# ARDUINO_UNO_CH340.net
KiCad netlist of a schematic drawn in Altium Designer
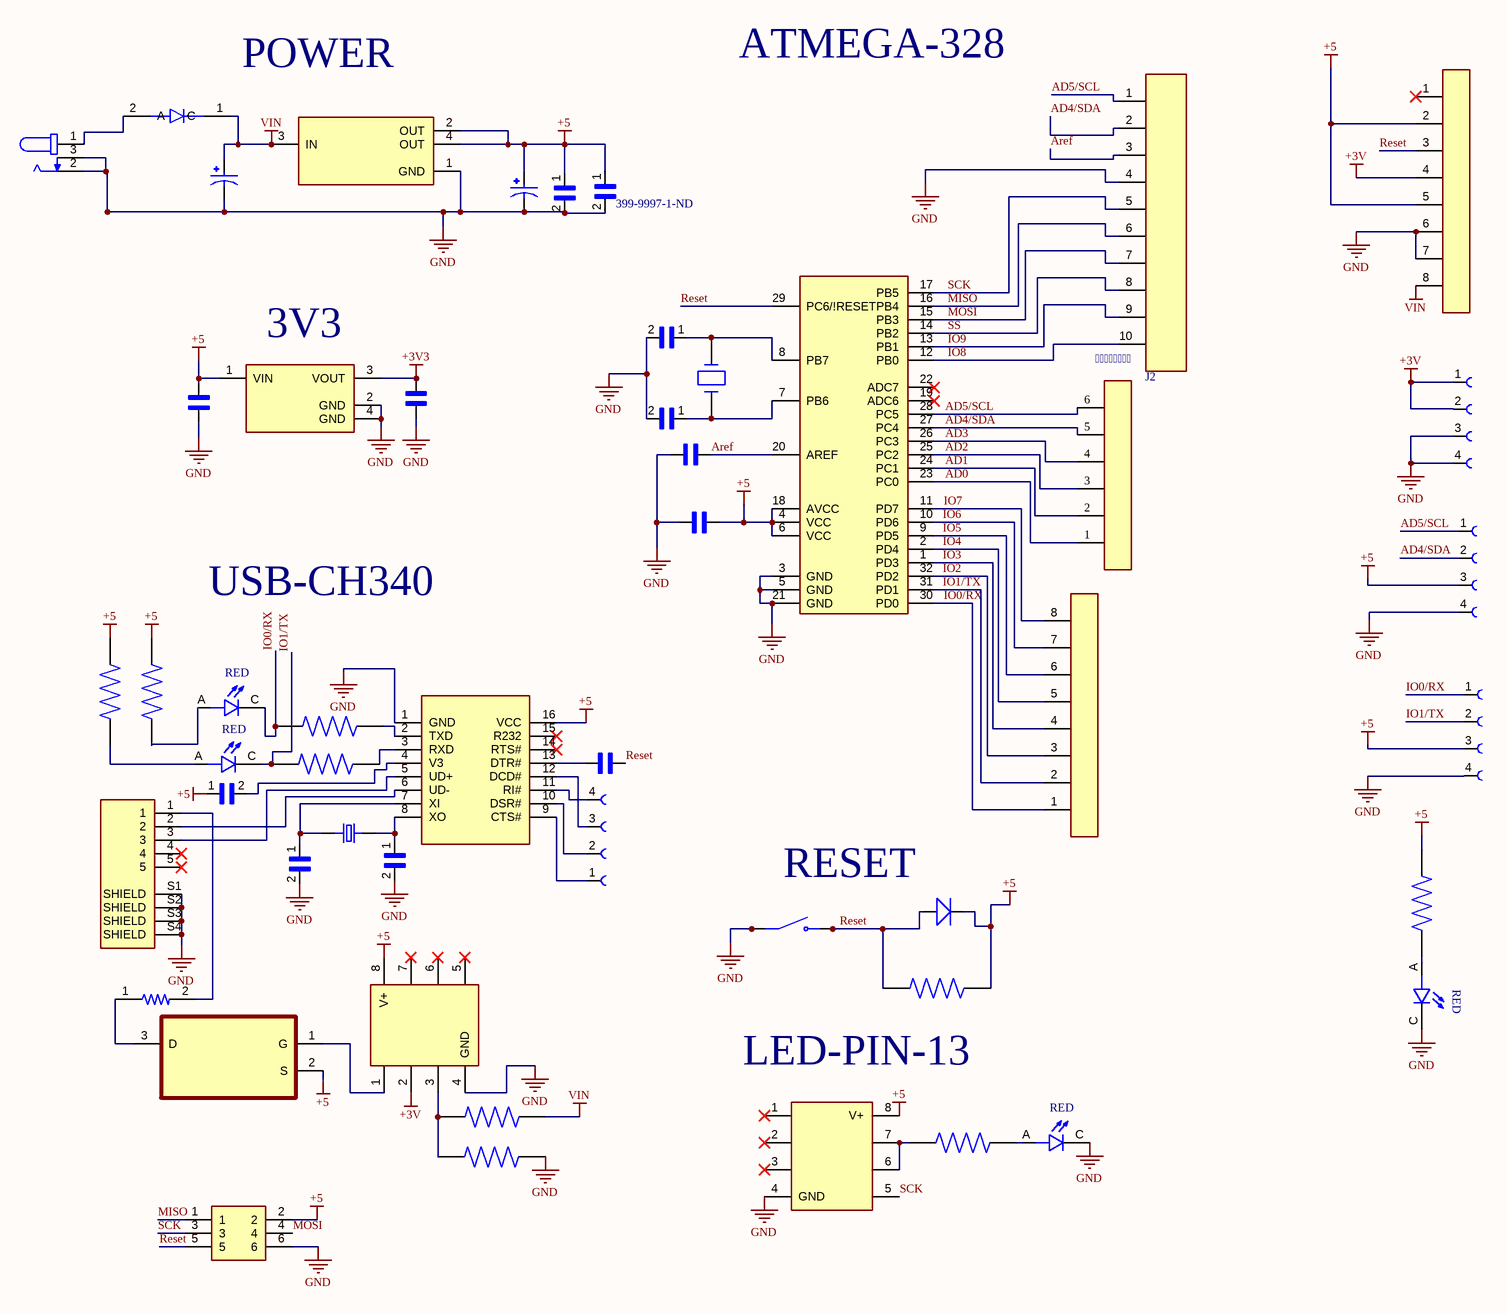
[diagram p0: ARDUINO_UNO_CH340.SchDoc]

(export (version "E")
  (design (tool "Eeschema 10.0.6"))
  (components
    (comp (ref "C1")
      (value "CAP ALUM 47UF 20% 25V SMD")
      (footprint "CAP_25SVPD47M")
      (description "47 µF 25 V Aluminum Electrolytic Capacitors Radial, Can - SMD - 3000 Hrs @ 105°C")
      (fields (field (name "MP") "25SVPD47M"))
      (libsource (lib "ARDUINO_UNO_CH340") (part "25SVPD47M"))
    )
    (comp (ref "C2")
      (value "CAP ALUM 47UF 20% 25V SMD")
      (footprint "CAP_25SVPD47M")
      (description "47 µF 25 V Aluminum Electrolytic Capacitors Radial, Can - SMD - 3000 Hrs @ 105°C")
      (fields (field (name "MP") "25SVPD47M"))
      (libsource (lib "ARDUINO_UNO_CH340") (part "25SVPD47M"))
    )
    (comp (ref "C3")
      (value "C0805J104K5RACTU")
      (footprint "CAPC2012X88N")
      (description "CAP MLCC, 0.1UF, 50V, X7R, 10%, 0805; Product Range: KEMET - J Series; Capacitance")
      (fields (field (name "MF") "KEMET"))
      (libsource (lib "ARDUINO_UNO_CH340") (part "C0805J104K5RACTU"))
    )
    (comp (ref "C4")
      (value "C0805J104K5RACTU")
      (footprint "CAPC2012X88N")
      (description "CAP MLCC, 0.1UF, 50V, X7R, 10%, 0805; Product Range: KEMET - J Series; Capacitance")
      (fields (field (name "MF") "KEMET") (field (name "SUPPLIER PART NUMBER 1") "399-9997-1-ND"))
      (libsource (lib "ARDUINO_UNO_CH340") (part "C0805J104K5RACTU"))
    )
    (comp (ref "C5")
      (value "CAP CER 25PF 100V NP0 0805")
      (footprint "CAPC2012X94N")
      (description "25 pF ±2% 100V Ceramic Capacitor C0G, NP0 0805 (2012 Metric)")
      (fields (field (name "MP") "08051A250GAT2A"))
      (libsource (lib "ARDUINO_UNO_CH340") (part "08051A250GAT2A"))
    )
    (comp (ref "C6")
      (value "CAP CER 25PF 100V NP0 0805")
      (footprint "CAPC2012X94N")
      (description "25 pF ±2% 100V Ceramic Capacitor C0G, NP0 0805 (2012 Metric)")
      (fields (field (name "MP") "08051A250GAT2A"))
      (libsource (lib "ARDUINO_UNO_CH340") (part "08051A250GAT2A"))
    )
    (comp (ref "C7")
      (value "885012209041")
      (footprint "WCAP-CSGP_885012209041")
      (libsource (lib "") (part "885012209041_1"))
    )
    (comp (ref "C8")
      (value "885012209041")
      (footprint "WCAP-CSGP_885012209041")
      (libsource (lib "") (part "885012209041_1"))
    )
    (comp (ref "C9")
      (value "885012209041")
      (footprint "WCAP-CSGP_885012209041")
      (libsource (lib "") (part "885012209041_2"))
    )
    (comp (ref "C10")
      (value "885012209041")
      (footprint "WCAP-CSGP_885012209041")
      (libsource (lib "ARDUINO_UNO_CH340") (part "885012209041"))
    )
    (comp (ref "C11")
      (value "CAP CER 0805 10NF 50V C0G 1%")
      (footprint "CAPC2012X88N")
      (description "±1% 50V Ceramic Capacitor C0G, NP0 0805 (2012 Metric)")
      (fields (field (name "MF") "KEMET") (field (name "MP") "C0805J104K5RACTU"))
      (libsource (lib "ARDUINO_UNO_CH340") (part "C0805C103F5GEC-ND"))
    )
    (comp (ref "C12")
      (value "885012209041")
      (footprint "WCAP-CSGP_885012209041")
      (libsource (lib "ARDUINO_UNO_CH340") (part "885012209041"))
    )
    (comp (ref "C13")
      (value "CAP CER 25PF 100V NP0 0805")
      (footprint "CAPC2012X94N")
      (description "25 pF ±2% 100V Ceramic Capacitor C0G, NP0 0805 (2012 Metric)")
      (fields (field (name "MP") "08051A250GAT2A"))
      (libsource (lib "") (part "08051A250GAT2A_1"))
    )
    (comp (ref "C14")
      (value "CAP CER 25PF 100V NP0 0805")
      (footprint "CAPC2012X94N")
      (description "25 pF ±2% 100V Ceramic Capacitor C0G, NP0 0805 (2012 Metric)")
      (fields (field (name "MP") "08051A250GAT2A"))
      (libsource (lib "") (part "08051A250GAT2A_1"))
    )
    (comp (ref "CO1")
      (value "CRYSTAL 16.0000MHZ 18PF SMD")
      (footprint "XTAL_ABLS2-24.000MHZ-D4YF-T")
      (description "24MHz Â±30ppm Crystal 18pF 40 Ohms HC-49/US")
      (fields (field (name "MP") "ABLS2-24.000MHZ-D4YF-T") (field (name "MF") "Abracon"))
      (libsource (lib "ARDUINO_UNO_CH340") (part "ABLS2-24.000MHZ-D4YF-T"))
    )
    (comp (ref "CP1")
      (value "CONN PWR JACK 2X5.5MM SOLDER")
      (footprint "POWERJACK_CUI_PJ-002A")
      (description "Power Barrel Connector Jack 2.10mm ID (0.083\"), 5.50mm OD (0.217\") Through Hole, Right Angle")
      (libsource (lib "ARDUINO_UNO_CH340") (part "CP-002A-ND"))
    )
    (comp (ref "D1")
      (value "S1M-FDITR-ND")
      (footprint "DIODE_DIOM4226X244N")
      (description "DIODE GEN PURP 1KV 1A SMA")
      (fields (field (name "MF") "ON Semiconductor") (field (name "MP") "ES1G"))
      (libsource (lib "ARDUINO_UNO_CH340") (part "DIODE_S1G"))
    )
    (comp (ref "D2")
      (value "7012X1")
      (footprint "LED_7012X1")
      (description "Red LED Indication - Discrete 1.7V 0805 (2012 Metric)")
      (libsource (lib "ARDUINO_UNO_CH340") (part "7012X1"))
    )
    (comp (ref "D3")
      (value "7012X1")
      (footprint "LED_7012X1")
      (description "Red LED Indication - Discrete 1.7V 0805 (2012 Metric)")
      (libsource (lib "ARDUINO_UNO_CH340") (part "7012X1"))
    )
    (comp (ref "D4")
      (value "DIODE GEN PURP 100V 150MA 1206")
      (footprint "DIODE")
      (description "Diode Standard 100V 150mA Surface Mount 1206")
      (fields (field (name "MP") "CD1206-S01575") (field (name "MF") "Bourns"))
      (libsource (lib "ARDUINO_UNO_CH340") (part "CD1206-S01575"))
    )
    (comp (ref "D5")
      (value "7012X1")
      (footprint "LED_7012X1")
      (description "Red LED Indication - Discrete 1.7V 0805 (2012 Metric)")
      (libsource (lib "ARDUINO_UNO_CH340") (part "7012X1"))
    )
    (comp (ref "D6")
      (value "7012X1")
      (footprint "LED_7012X1")
      (description "Red LED Indication - Discrete 1.7V 0805 (2012 Metric)")
      (libsource (lib "ARDUINO_UNO_CH340") (part "7012X1"))
    )
    (comp (ref "J1")
      (value "Conn_Sullins_PPTC081LFBN-RC_eec")
      (footprint "Sullins_PPTC081LFBN-RC_0")
      (description "CONN HEADER FEMALE 8POS .1\" TIN")
      (fields (field (name "MANUFACTURER") "Sullins") (field (name "DIGIKEY PART NUMBER") "S7006-ND"))
      (libsource (lib "ARDUINO_UNO_CH340") (part "Conn_Sullins_PPTC081LFBN-RC_eec"))
    )
    (comp (ref "J2")
      (value "Conn_Sullins_PPTC101LFBN-RC_eec")
      (footprint "Sullins_PPTC101LFBN-RC_0 - duplicate2")
      (description "CONN HEADER FEMALE 10POS.1\" TIN")
      (fields
        (field (name "MANUFACTURER") "Sullins")
        (field (name "OCTOPART PART NUMBER") "a3ed6ae3a4397c2a")
      )
      (libsource (lib "ARDUINO_UNO_CH340") (part "Conn_Sullins_PPTC101LFBN-RC_eec"))
    )
    (comp (ref "J3")
      (value "PPTC061LFBN-RC")
      (footprint "Sullins_PPTC061LFBN-RC_0")
      (libsource (lib "ARDUINO_UNO_CH340") (part "PPTC061LFBN-RC"))
    )
    (comp (ref "J4")
      (value "Conn_Sullins_PPTC081LFBN-RC_eec")
      (footprint "Sullins_PPTC081LFBN-RC_0")
      (description "CONN HEADER FEMALE 8POS .1\" TIN")
      (fields (field (name "MANUFACTURER") "Sullins") (field (name "DIGIKEY PART NUMBER") "S7006-ND"))
      (libsource (lib "") (part "Conn_Sullins_PPTC081LFBN-RC_eec_1"))
    )
    (comp (ref "J5")
      (value "1734035-4")
      (footprint "J_SMD_1734035-4-5_0.8_9.9_8.85_3.9")
      (description "Conn Mini USB 2.0 Type B RCP 5 POS 0.8mm Solder RA SMD 5 Terminal 1 Port Automotive T/R")
      (fields (field (name "MF") "TE Connectivity") (field (name "DIGI-KEY_PART_NUMBER") "A121554CT-ND"))
      (libsource (lib "ARDUINO_UNO_CH340") (part "1734035-4"))
    )
    (comp (ref "J6")
      (value "67997-206HLF")
      (footprint "FRAMATOME_67997-206HLF")
      (description "Connector Header Through Hole 6 position 0.100 _2.54mm_")
      (fields (field (name "MF") "Amphenol ICC") (field (name "DIGI-KEY_PART_NUMBER") "609-3234-ND"))
      (libsource (lib "ARDUINO_UNO_CH340") (part "67997-206HLF"))
    )
    (comp (ref "K1")
      (value "61300411121")
      (footprint "61300411121")
      (description "Connector Header Through Hole 4 position 0.100 (2.54mm)")
      (fields (field (name "MF") "WÃ¼rth Elektronik"))
      (libsource (lib "ARDUINO_UNO_CH340") (part "61300411121"))
    )
    (comp (ref "K2")
      (value "61300411121")
      (footprint "61300411121")
      (description "Connector Header Through Hole 4 position 0.100 (2.54mm)")
      (fields (field (name "MF") "WÃ¼rth Elektronik"))
      (libsource (lib "ARDUINO_UNO_CH340") (part "61300411121"))
    )
    (comp (ref "K3")
      (value "61300411121")
      (footprint "61300411121")
      (description "Connector Header Through Hole 4 position 0.100 (2.54mm)")
      (fields (field (name "MF") "WÃ¼rth Elektronik"))
      (libsource (lib "ARDUINO_UNO_CH340") (part "61300411121"))
    )
    (comp (ref "K4")
      (value "61300411121")
      (footprint "61300411121")
      (description "Connector Header Through Hole 4 position 0.100 (2.54mm)")
      (fields (field (name "MF") "WÃ¼rth Elektronik"))
      (libsource (lib "") (part "61300411121_1"))
    )
    (comp (ref "MC1")
      (value "ATMEGA328P-AU")
      (footprint "QFP80P900X900X120-32N")
      (description "AVR AVRÂ® ATmega Microcontroller IC 8-Bit 20MHz 32KB _16K x 16_ FLASH 32-TQFP _7x7_")
      (fields (field (name "MF") "Microchip"))
      (libsource (lib "ARDUINO_UNO_CH340") (part "ATMEGA328P-AU"))
    )
    (comp (ref "R1")
      (value "1kOhm,0805,1%,50ppm, 100mW,100VRN732ATTDK1001F50")
      (footprint "RESC2012X60N")
      (description "Thin Film Resistors - SMD 1kOhm,0805,1%,50ppm, 100mW,100V")
      (fields (field (name "MP") "RN732ATTDK1001F50"))
      (libsource (lib "ARDUINO_UNO_CH340") (part "1kOhm,0805,1%,50ppm, 100mW,100VRN732ATTDK1001F50"))
    )
    (comp (ref "R2")
      (value "1kOhm,0805,1%,50ppm, 100mW,100VRN732ATTDK1001F50")
      (footprint "RESC2012X60N")
      (description "Thin Film Resistors - SMD 1kOhm,0805,1%,50ppm, 100mW,100V")
      (fields (field (name "MP") "RN732ATTDK1001F50"))
      (libsource (lib "ARDUINO_UNO_CH340") (part "1kOhm,0805,1%,50ppm, 100mW,100VRN732ATTDK1001F50"))
    )
    (comp (ref "R3")
      (value "1kOhm,0805,1%,50ppm, 100mW,100VRN732ATTDK1001F50")
      (footprint "RESC2012X60N")
      (description "Thin Film Resistors - SMD 1kOhm,0805,1%,50ppm, 100mW,100V")
      (fields (field (name "MP") "RN732ATTDK1001F50"))
      (libsource (lib "ARDUINO_UNO_CH340") (part "1kOhm,0805,1%,50ppm, 100mW,100VRN732ATTDK1001F50"))
    )
    (comp (ref "R4")
      (value "1kOhm,0805,1%,50ppm, 100mW,100VRN732ATTDK1001F50")
      (footprint "RESC2012X60N")
      (description "Thin Film Resistors - SMD 1kOhm,0805,1%,50ppm, 100mW,100V")
      (fields (field (name "MP") "RN732ATTDK1001F50"))
      (libsource (lib "ARDUINO_UNO_CH340") (part "1kOhm,0805,1%,50ppm, 100mW,100VRN732ATTDK1001F50"))
    )
    (comp (ref "R5")
      (value "1kOhm,0805,1%,50ppm, 100mW,100VRN732ATTDK1001F50")
      (footprint "RESC2012X60N")
      (description "Thin Film Resistors - SMD 1kOhm,0805,1%,50ppm, 100mW,100V")
      (fields (field (name "MP") "RN732ATTDK1001F50"))
      (libsource (lib "ARDUINO_UNO_CH340") (part "1kOhm,0805,1%,50ppm, 100mW,100VRN732ATTDK1001F50"))
    )
    (comp (ref "R6")
      (value "1kOhm,0805,1%,50ppm, 100mW,100VRN732ATTDK1001F50")
      (footprint "RESC2012X60N")
      (description "Thin Film Resistors - SMD 1kOhm,0805,1%,50ppm, 100mW,100V")
      (fields (field (name "MP") "RN732ATTDK1001F50"))
      (libsource (lib "ARDUINO_UNO_CH340") (part "1kOhm,0805,1%,50ppm, 100mW,100VRN732ATTDK1001F50"))
    )
    (comp (ref "R7")
      (value "PICOSMDC050S-2")
      (footprint "RESC2012X60N")
      (description "Polymeric PTC Resettable Fuse 6V 500mA Ih Surface Mount 0805 _2012 Metric_, Concave")
      (fields (field (name "MF") "Littelfuse Inc."))
      (libsource (lib "ARDUINO_UNO_CH340") (part "PICOSMDC050S-2"))
    )
    (comp (ref "R8")
      (value "CRGCQ0805F10K")
      (footprint "RESC2012X65N")
      (description "Fixed Resistor CRGCQ 0805 10K 1%")
      (fields (field (name "MF") "TE Connectivity"))
      (libsource (lib "ARDUINO_UNO_CH340") (part "CRGCQ0805F10K"))
    )
    (comp (ref "R9")
      (value "CRGCQ0805F10K")
      (footprint "RESC2012X65N")
      (description "Fixed Resistor CRGCQ 0805 10K 1%")
      (fields (field (name "MF") "TE Connectivity"))
      (libsource (lib "ARDUINO_UNO_CH340") (part "CRGCQ0805F10K"))
    )
    (comp (ref "R10")
      (value "1kOhm,0805,1%,50ppm, 100mW,100VRN732ATTDK1001F50")
      (footprint "RESC2012X60N")
      (description "Thin Film Resistors - SMD 1kOhm,0805,1%,50ppm, 100mW,100V")
      (fields (field (name "MP") "RN732ATTDK1001F50"))
      (libsource (lib "ARDUINO_UNO_CH340") (part "1kOhm,0805,1%,50ppm, 100mW,100VRN732ATTDK1001F50"))
    )
    (comp (ref "S1")
      (value "2-1437565-8")
      (footprint "SW_2-1437565-8")
      (description "Tactile Switch SPST-NO Top Actuated Surface Mount")
      (fields (field (name "MF") "TE Connectivity"))
      (libsource (lib "ARDUINO_UNO_CH340") (part "2-1437565-8"))
    )
    (comp (ref "U1")
      (value "NCP1117ST50T3G")
      (footprint "SOT230P700X180-4N")
      (description "Linear Voltage Regulator IC 1 Output 1A SOT-223")
      (fields (field (name "MF") "ON Semiconductor"))
      (libsource (lib "ARDUINO_UNO_CH340") (part "NCP1117ST50T3G"))
    )
    (comp (ref "U2")
      (value "MCP1703T-3302E/DB")
      (footprint "SOT230P700X180-4N - duplicate")
      (description "Linear Voltage Regulator IC 1 Output 250mA SOT-223-3")
      (fields (field (name "MF") "Microchip"))
      (libsource (lib "ARDUINO_UNO_CH340") (part "MCP1703T-3302E/DB"))
    )
    (comp (ref "U3")
      (value "CH340 USB 2.0 to UART Interface Evaluation Board")
      (footprint "SO16")
      (fields (field (name "MF") "DFRobot") (field (name "MP") "CH340"))
      (libsource (lib "ARDUINO_UNO_CH340") (part "CH340"))
    )
    (comp (ref "U4")
      (value "LM358M/NOPB")
      (footprint "SOIC127P599X175-8N")
      (description "2-Channel, 1MHz, industry standard, 32V op amp 8-SOIC 0 to 70")
      (fields
        (field (name "DIGI-KEY_PART_NUMBER") "LM358MX/NOPBTR-ND")
        (field (name "MF") "Texas Instruments")
      )
      (libsource (lib "") (part "LM358M/NOPB_1"))
    )
    (comp (ref "U5")
      (value "SI2301BDS-T1-E3")
      (footprint "SOT95P237X112-3N")
      (description "P-Channel 20V 2.2A _Ta_ 700mW _Ta_ Surface Mount SOT-23-3 _TO-236_")
      (fields (field (name "MF") "Vishay"))
      (libsource (lib "ARDUINO_UNO_CH340") (part "SI2301BDS-T1-E3"))
    )
    (comp (ref "U6")
      (value "LM358M/NOPB")
      (footprint "SOIC127P599X175-8N")
      (description "2-Channel, 1MHz, industry standard, 32V op amp 8-SOIC 0 to 70")
      (fields
        (field (name "DIGI-KEY_PART_NUMBER") "LM358MX/NOPBTR-ND")
        (field (name "MF") "Texas Instruments")
      )
      (libsource (lib "ARDUINO_UNO_CH340") (part "LM358M/NOPB"))
    )
    (comp (ref "Y1")
      (value "ECS-120-S-5PX-TR")
      (footprint "XTAL_ECS-120-S-5PX-TR")
      (description "12MHz Â±30ppm Crystal Series 50 Ohms HC-49/US")
      (fields (field (name "MF") "ECS Inc."))
      (libsource (lib "ARDUINO_UNO_CH340") (part "ECS-120-S-5PX-TR"))
    )
  )
  (nets
    (net (code "1") (name "+3V") (class "Default")
      (node (ref "J1") (pin "4") (pinfunction "4_4") (pintype "passive"))
      (node (ref "K1") (pin "1") (pinfunction "1_1") (pintype "passive"))
      (node (ref "K1") (pin "2") (pinfunction "2_2") (pintype "passive"))
      (node (ref "U4") (pin "2") (pinfunction "-INA_2") (pintype "passive"))
    )
    (net (code "2") (name "+3V3") (class "Default")
      (node (ref "C7") (pin "2") (pinfunction "2_2") (pintype "passive"))
      (node (ref "U2") (pin "3") (pinfunction "VOUT_3") (pintype "passive"))
    )
    (net (code "3") (name "+5") (class "Default")
      (node (ref "C10") (pin "1") (pinfunction "1_1") (pintype "passive"))
      (node (ref "C11") (pin "1") (pinfunction "1_1") (pintype "passive"))
      (node (ref "C2") (pin "1") (pinfunction "1_1") (pintype "passive"))
      (node (ref "C3") (pin "1") (pinfunction "1_1") (pintype "passive"))
      (node (ref "C4") (pin "1") (pinfunction "1_1") (pintype "passive"))
      (node (ref "C8") (pin "2") (pinfunction "2_2") (pintype "passive"))
      (node (ref "D4") (pin "NEG") (pinfunction "NEG_NEG") (pintype "passive"))
      (node (ref "J1") (pin "2") (pinfunction "2_2") (pintype "passive"))
      (node (ref "J1") (pin "5") (pinfunction "5_5") (pintype "passive"))
      (node (ref "J6") (pin "2") (pinfunction "2_2") (pintype "passive"))
      (node (ref "K2") (pin "3") (pinfunction "3_3") (pintype "passive"))
      (node (ref "K3") (pin "3") (pinfunction "3_3") (pintype "passive"))
      (node (ref "MC1") (pin "18") (pinfunction "AVCC_18") (pintype "power_in"))
      (node (ref "MC1") (pin "4") (pinfunction "VCC_4") (pintype "power_in"))
      (node (ref "MC1") (pin "6") (pinfunction "VCC_6") (pintype "power_in"))
      (node (ref "R1") (pin "2") (pinfunction "2_2") (pintype "passive"))
      (node (ref "R2") (pin "1") (pinfunction "1_1") (pintype "passive"))
      (node (ref "R5") (pin "1") (pinfunction "1_1") (pintype "passive"))
      (node (ref "R6") (pin "2") (pinfunction "2_2") (pintype "passive"))
      (node (ref "U1") (pin "2") (pinfunction "OUT_2") (pintype "passive"))
      (node (ref "U1") (pin "4") (pinfunction "OUT_4") (pintype "passive"))
      (node (ref "U2") (pin "1") (pinfunction "VIN_1") (pintype "passive"))
      (node (ref "U3") (pin "16") (pinfunction "VCC_16") (pintype "power_in"))
      (node (ref "U4") (pin "8") (pinfunction "V+_8") (pintype "power_in"))
      (node (ref "U5") (pin "2") (pinfunction "S_2") (pintype "passive"))
      (node (ref "U6") (pin "8") (pinfunction "V+_8") (pintype "power_in"))
    )
    (net (code "4") (name "/AD0") (class "Default")
      (node (ref "J3") (pin "1") (pinfunction "1_1") (pintype "passive"))
      (node (ref "MC1") (pin "23") (pinfunction "PC0_23") (pintype "passive"))
    )
    (net (code "5") (name "/AD1") (class "Default")
      (node (ref "J3") (pin "2") (pinfunction "2_2") (pintype "passive"))
      (node (ref "MC1") (pin "24") (pinfunction "PC1_24") (pintype "passive"))
    )
    (net (code "6") (name "/AD2") (class "Default")
      (node (ref "J3") (pin "3") (pinfunction "3_3") (pintype "passive"))
      (node (ref "MC1") (pin "25") (pinfunction "PC2_25") (pintype "passive"))
    )
    (net (code "7") (name "/AD3") (class "Default")
      (node (ref "J3") (pin "4") (pinfunction "4_4") (pintype "passive"))
      (node (ref "MC1") (pin "26") (pinfunction "PC3_26") (pintype "passive"))
    )
    (net (code "8") (name "/AD4{slash}SDA") (class "Default")
      (node (ref "J2") (pin "2") (pinfunction "2_2") (pintype "passive"))
      (node (ref "J3") (pin "5") (pinfunction "5_5") (pintype "passive"))
      (node (ref "K2") (pin "2") (pinfunction "2_2") (pintype "passive"))
      (node (ref "MC1") (pin "27") (pinfunction "PC4_27") (pintype "passive"))
    )
    (net (code "9") (name "/AD5{slash}SCL") (class "Default")
      (node (ref "J2") (pin "1") (pinfunction "1_1") (pintype "passive"))
      (node (ref "J3") (pin "6") (pinfunction "6_6") (pintype "passive"))
      (node (ref "K2") (pin "1") (pinfunction "1_1") (pintype "passive"))
      (node (ref "MC1") (pin "28") (pinfunction "PC5_28") (pintype "passive"))
    )
    (net (code "10") (name "/Aref") (class "Default")
      (node (ref "C9") (pin "2") (pinfunction "2_2") (pintype "passive"))
      (node (ref "J2") (pin "3") (pinfunction "3_3") (pintype "passive"))
      (node (ref "MC1") (pin "20") (pinfunction "AREF_20") (pintype "passive"))
    )
    (net (code "11") (name "/IO0{slash}RX") (class "Default")
      (node (ref "D2") (pin "C") (pinfunction "C_C") (pintype "passive"))
      (node (ref "J4") (pin "1") (pinfunction "1_1") (pintype "passive"))
      (node (ref "K3") (pin "1") (pinfunction "1_1") (pintype "passive"))
      (node (ref "MC1") (pin "30") (pinfunction "PD0_30") (pintype "passive"))
      (node (ref "R3") (pin "1") (pinfunction "1_1") (pintype "passive"))
    )
    (net (code "12") (name "/IO1{slash}TX") (class "Default")
      (node (ref "D3") (pin "C") (pinfunction "C_C") (pintype "passive"))
      (node (ref "J4") (pin "2") (pinfunction "2_2") (pintype "passive"))
      (node (ref "K3") (pin "2") (pinfunction "2_2") (pintype "passive"))
      (node (ref "MC1") (pin "31") (pinfunction "PD1_31") (pintype "passive"))
      (node (ref "R4") (pin "1") (pinfunction "1_1") (pintype "passive"))
    )
    (net (code "13") (name "/IO2") (class "Default")
      (node (ref "J4") (pin "3") (pinfunction "3_3") (pintype "passive"))
      (node (ref "MC1") (pin "32") (pinfunction "PD2_32") (pintype "passive"))
    )
    (net (code "14") (name "/IO3") (class "Default")
      (node (ref "J4") (pin "4") (pinfunction "4_4") (pintype "passive"))
      (node (ref "MC1") (pin "1") (pinfunction "PD3_1") (pintype "passive"))
    )
    (net (code "15") (name "/IO4") (class "Default")
      (node (ref "J4") (pin "5") (pinfunction "5_5") (pintype "passive"))
      (node (ref "MC1") (pin "2") (pinfunction "PD4_2") (pintype "passive"))
    )
    (net (code "16") (name "/IO5") (class "Default")
      (node (ref "J4") (pin "6") (pinfunction "6_6") (pintype "passive"))
      (node (ref "MC1") (pin "9") (pinfunction "PD5_9") (pintype "passive"))
    )
    (net (code "17") (name "/IO6") (class "Default")
      (node (ref "J4") (pin "7") (pinfunction "7_7") (pintype "passive"))
      (node (ref "MC1") (pin "10") (pinfunction "PD6_10") (pintype "passive"))
    )
    (net (code "18") (name "/IO7") (class "Default")
      (node (ref "J4") (pin "8") (pinfunction "8_8") (pintype "passive"))
      (node (ref "MC1") (pin "11") (pinfunction "PD7_11") (pintype "passive"))
    )
    (net (code "19") (name "/IO8") (class "Default")
      (node (ref "J2") (pin "10") (pinfunction "10_10") (pintype "passive"))
      (node (ref "MC1") (pin "12") (pinfunction "PB0_12") (pintype "passive"))
    )
    (net (code "20") (name "/IO9") (class "Default")
      (node (ref "J2") (pin "9") (pinfunction "9_9") (pintype "passive"))
      (node (ref "MC1") (pin "13") (pinfunction "PB1_13") (pintype "passive"))
    )
    (net (code "21") (name "/MISO") (class "Default")
      (node (ref "J2") (pin "6") (pinfunction "6_6") (pintype "passive"))
      (node (ref "J6") (pin "1") (pinfunction "1_1") (pintype "passive"))
      (node (ref "MC1") (pin "16") (pinfunction "PB4_16") (pintype "passive"))
    )
    (net (code "22") (name "/MOSI") (class "Default")
      (node (ref "J2") (pin "7") (pinfunction "7_7") (pintype "passive"))
      (node (ref "J6") (pin "4") (pinfunction "4_4") (pintype "passive"))
      (node (ref "MC1") (pin "15") (pinfunction "PB3_15") (pintype "passive"))
    )
    (net (code "23") (name "/Reset") (class "Default")
      (node (ref "C12") (pin "1") (pinfunction "1_1") (pintype "passive"))
      (node (ref "D4") (pin "POS") (pinfunction "POS_POS") (pintype "passive"))
      (node (ref "J1") (pin "3") (pinfunction "3_3") (pintype "passive"))
      (node (ref "J6") (pin "5") (pinfunction "5_5") (pintype "passive"))
      (node (ref "MC1") (pin "29") (pinfunction "PC6/!RESET_29") (pintype "passive"))
      (node (ref "R6") (pin "1") (pinfunction "1_1") (pintype "passive"))
      (node (ref "S1") (pin "3") (pinfunction "NO_3") (pintype "passive"))
      (node (ref "S1") (pin "4") (pinfunction "NO_4") (pintype "passive"))
    )
    (net (code "24") (name "/SCK") (class "Default")
      (node (ref "J2") (pin "5") (pinfunction "5_5") (pintype "passive"))
      (node (ref "J6") (pin "3") (pinfunction "3_3") (pintype "passive"))
      (node (ref "MC1") (pin "17") (pinfunction "PB5_17") (pintype "passive"))
      (node (ref "U6") (pin "5") (pinfunction "+INB_5") (pintype "passive"))
    )
    (net (code "25") (name "/SS") (class "Default")
      (node (ref "J2") (pin "8") (pinfunction "8_8") (pintype "passive"))
      (node (ref "MC1") (pin "14") (pinfunction "PB2_14") (pintype "passive"))
    )
    (net (code "26") (name "GND") (class "Default")
      (node (ref "C1") (pin "2") (pinfunction "2_2") (pintype "passive"))
      (node (ref "C10") (pin "2") (pinfunction "2_2") (pintype "passive"))
      (node (ref "C13") (pin "2") (pinfunction "2_2") (pintype "passive"))
      (node (ref "C14") (pin "2") (pinfunction "2_2") (pintype "passive"))
      (node (ref "C2") (pin "2") (pinfunction "2_2") (pintype "passive"))
      (node (ref "C3") (pin "2") (pinfunction "2_2") (pintype "passive"))
      (node (ref "C4") (pin "2") (pinfunction "2_2") (pintype "passive"))
      (node (ref "C5") (pin "2") (pinfunction "2_2") (pintype "passive"))
      (node (ref "C6") (pin "2") (pinfunction "2_2") (pintype "passive"))
      (node (ref "C7") (pin "1") (pinfunction "1_1") (pintype "passive"))
      (node (ref "C8") (pin "1") (pinfunction "1_1") (pintype "passive"))
      (node (ref "C9") (pin "1") (pinfunction "1_1") (pintype "passive"))
      (node (ref "CP1") (pin "2") (pinfunction "2_2") (pintype "passive"))
      (node (ref "CP1") (pin "3") (pinfunction "3_3") (pintype "passive"))
      (node (ref "D5") (pin "C") (pinfunction "C_C") (pintype "passive"))
      (node (ref "D6") (pin "C") (pinfunction "C_C") (pintype "passive"))
      (node (ref "J1") (pin "6") (pinfunction "6_6") (pintype "passive"))
      (node (ref "J1") (pin "7") (pinfunction "7_7") (pintype "passive"))
      (node (ref "J2") (pin "4") (pinfunction "4_4") (pintype "passive"))
      (node (ref "J5") (pin "S1") (pinfunction "SHIELD_S1") (pintype "passive"))
      (node (ref "J5") (pin "S2") (pinfunction "SHIELD_S2") (pintype "passive"))
      (node (ref "J5") (pin "S3") (pinfunction "SHIELD_S3") (pintype "passive"))
      (node (ref "J5") (pin "S4") (pinfunction "SHIELD_S4") (pintype "passive"))
      (node (ref "J6") (pin "6") (pinfunction "6_6") (pintype "passive"))
      (node (ref "K1") (pin "3") (pinfunction "3_3") (pintype "passive"))
      (node (ref "K1") (pin "4") (pinfunction "4_4") (pintype "passive"))
      (node (ref "K2") (pin "4") (pinfunction "4_4") (pintype "passive"))
      (node (ref "K3") (pin "4") (pinfunction "4_4") (pintype "passive"))
      (node (ref "MC1") (pin "21") (pinfunction "GND_21") (pintype "power_in"))
      (node (ref "MC1") (pin "3") (pinfunction "GND_3") (pintype "power_in"))
      (node (ref "MC1") (pin "5") (pinfunction "GND_5") (pintype "power_in"))
      (node (ref "R9") (pin "2") (pinfunction "2_2") (pintype "passive"))
      (node (ref "S1") (pin "1") (pinfunction "COM_1") (pintype "passive"))
      (node (ref "S1") (pin "2") (pinfunction "COM_2") (pintype "passive"))
      (node (ref "U1") (pin "1") (pinfunction "GND_1") (pintype "power_in"))
      (node (ref "U2") (pin "2") (pinfunction "GND_2") (pintype "power_in"))
      (node (ref "U2") (pin "4") (pinfunction "GND_4") (pintype "power_in"))
      (node (ref "U3") (pin "1") (pinfunction "GND_1") (pintype "power_in"))
      (node (ref "U4") (pin "4") (pinfunction "GND_4") (pintype "power_in"))
      (node (ref "U6") (pin "4") (pinfunction "GND_4") (pintype "power_in"))
    )
    (net (code "27") (name "Net-(D1-A)") (class "Default")
      (node (ref "CP1") (pin "1") (pinfunction "1_1") (pintype "passive"))
      (node (ref "D1") (pin "2") (pinfunction "A_2") (pintype "passive"))
    )
    (net (code "28") (name "Net-(D2-PadA)") (class "Default")
      (node (ref "D2") (pin "A") (pinfunction "A_A") (pintype "passive"))
      (node (ref "R2") (pin "2") (pinfunction "2_2") (pintype "passive"))
    )
    (net (code "29") (name "Net-(D3-PadA)") (class "Default")
      (node (ref "D3") (pin "A") (pinfunction "A_A") (pintype "passive"))
      (node (ref "R1") (pin "1") (pinfunction "1_1") (pintype "passive"))
    )
    (net (code "30") (name "Net-(D5-PadA)") (class "Default")
      (node (ref "D5") (pin "A") (pinfunction "A_A") (pintype "passive"))
      (node (ref "R5") (pin "2") (pinfunction "2_2") (pintype "passive"))
    )
    (net (code "31") (name "Net-(D6-PadA)") (class "Default")
      (node (ref "D6") (pin "A") (pinfunction "A_A") (pintype "passive"))
      (node (ref "R10") (pin "2") (pinfunction "2_2") (pintype "passive"))
    )
    (net (code "32") (name "Net-(J5-Pad1)") (class "Default")
      (node (ref "J5") (pin "1") (pinfunction "1_1") (pintype "passive"))
      (node (ref "R7") (pin "2") (pinfunction "2_2") (pintype "passive"))
    )
    (net (code "33") (name "Net-(MC1-PB6)") (class "Default")
      (node (ref "C6") (pin "1") (pinfunction "1_1") (pintype "passive"))
      (node (ref "CO1") (pin "2") (pinfunction "2_2") (pintype "passive"))
      (node (ref "MC1") (pin "7") (pinfunction "PB6_7") (pintype "passive"))
    )
    (net (code "34") (name "Net-(MC1-PB7)") (class "Default")
      (node (ref "C5") (pin "1") (pinfunction "1_1") (pintype "passive"))
      (node (ref "CO1") (pin "1") (pinfunction "1_1") (pintype "passive"))
      (node (ref "MC1") (pin "8") (pinfunction "PB7_8") (pintype "passive"))
    )
    (net (code "35") (name "Net-(U3-CTS#)") (class "Default")
      (node (ref "K4") (pin "1") (pinfunction "1_1") (pintype "passive"))
      (node (ref "U3") (pin "9") (pinfunction "CTS#_9") (pintype "passive"))
    )
    (net (code "36") (name "Net-(U3-DCD#)") (class "Default")
      (node (ref "K4") (pin "3") (pinfunction "3_3") (pintype "passive"))
      (node (ref "U3") (pin "12") (pinfunction "DCD#_12") (pintype "passive"))
    )
    (net (code "37") (name "Net-(U3-DSR#)") (class "Default")
      (node (ref "K4") (pin "2") (pinfunction "2_2") (pintype "passive"))
      (node (ref "U3") (pin "10") (pinfunction "DSR#_10") (pintype "passive"))
    )
    (net (code "38") (name "Net-(U3-DTR#)") (class "Default")
      (node (ref "C12") (pin "2") (pinfunction "2_2") (pintype "passive"))
      (node (ref "U3") (pin "13") (pinfunction "DTR#_13") (pintype "passive"))
    )
    (net (code "39") (name "Net-(U3-RI#)") (class "Default")
      (node (ref "K4") (pin "4") (pinfunction "4_4") (pintype "passive"))
      (node (ref "U3") (pin "11") (pinfunction "RI#_11") (pintype "passive"))
    )
    (net (code "40") (name "Net-(U3-RXD)") (class "Default")
      (node (ref "R4") (pin "2") (pinfunction "2_2") (pintype "passive"))
      (node (ref "U3") (pin "3") (pinfunction "RXD_3") (pintype "passive"))
    )
    (net (code "41") (name "Net-(U3-TXD)") (class "Default")
      (node (ref "R3") (pin "2") (pinfunction "2_2") (pintype "passive"))
      (node (ref "U3") (pin "2") (pinfunction "TXD_2") (pintype "passive"))
    )
    (net (code "42") (name "Net-(U3-UD+)") (class "Default")
      (node (ref "J5") (pin "3") (pinfunction "3_3") (pintype "passive"))
      (node (ref "U3") (pin "5") (pinfunction "UD+_5") (pintype "passive"))
    )
    (net (code "43") (name "Net-(U3-UD-)") (class "Default")
      (node (ref "J5") (pin "2") (pinfunction "2_2") (pintype "passive"))
      (node (ref "U3") (pin "6") (pinfunction "UD-_6") (pintype "passive"))
    )
    (net (code "44") (name "Net-(U3-V3)") (class "Default")
      (node (ref "C11") (pin "2") (pinfunction "2_2") (pintype "passive"))
      (node (ref "U3") (pin "4") (pinfunction "V3_4") (pintype "passive"))
    )
    (net (code "45") (name "Net-(U3-XI)") (class "Default")
      (node (ref "C14") (pin "1") (pinfunction "1_1") (pintype "passive"))
      (node (ref "U3") (pin "7") (pinfunction "XI_7") (pintype "passive"))
      (node (ref "Y1") (pin "1") (pinfunction "1_1") (pintype "passive"))
    )
    (net (code "46") (name "Net-(U3-XO)") (class "Default")
      (node (ref "C13") (pin "1") (pinfunction "1_1") (pintype "passive"))
      (node (ref "U3") (pin "8") (pinfunction "XO_8") (pintype "passive"))
      (node (ref "Y1") (pin "2") (pinfunction "2_2") (pintype "passive"))
    )
    (net (code "47") (name "Net-(U4-+INA)") (class "Default")
      (node (ref "R8") (pin "1") (pinfunction "1_1") (pintype "passive"))
      (node (ref "R9") (pin "1") (pinfunction "1_1") (pintype "passive"))
      (node (ref "U4") (pin "3") (pinfunction "+INA_3") (pintype "passive"))
    )
    (net (code "48") (name "Net-(U4-OUTA)") (class "Default")
      (node (ref "U4") (pin "1") (pinfunction "OUTA_1") (pintype "passive"))
      (node (ref "U5") (pin "1") (pinfunction "G_1") (pintype "passive"))
    )
    (net (code "49") (name "Net-(U5-D)") (class "Default")
      (node (ref "R7") (pin "1") (pinfunction "1_1") (pintype "passive"))
      (node (ref "U5") (pin "3") (pinfunction "D_3") (pintype "passive"))
    )
    (net (code "50") (name "Net-(U6--INB)") (class "Default")
      (node (ref "R10") (pin "1") (pinfunction "1_1") (pintype "passive"))
      (node (ref "U6") (pin "6") (pinfunction "-INB_6") (pintype "passive"))
      (node (ref "U6") (pin "7") (pinfunction "OUTB_7") (pintype "passive"))
    )
    (net (code "51") (name "VIN") (class "Default")
      (node (ref "C1") (pin "1") (pinfunction "1_1") (pintype "passive"))
      (node (ref "D1") (pin "1") (pinfunction "C_1") (pintype "passive"))
      (node (ref "J1") (pin "8") (pinfunction "8_8") (pintype "passive"))
      (node (ref "R8") (pin "2") (pinfunction "2_2") (pintype "passive"))
      (node (ref "U1") (pin "3") (pinfunction "IN_3") (pintype "passive"))
    )
    (net (code "52") (name "unconnected-(J1-Pad1)") (class "Default")
      (node (ref "J1") (pin "1") (pinfunction "1_1") (pintype "passive+no_connect"))
    )
    (net (code "53") (name "unconnected-(J5-Pad4)") (class "Default")
      (node (ref "J5") (pin "4") (pinfunction "4_4") (pintype "passive+no_connect"))
    )
    (net (code "54") (name "unconnected-(J5-Pad5)") (class "Default")
      (node (ref "J5") (pin "5") (pinfunction "5_5") (pintype "passive+no_connect"))
    )
    (net (code "55") (name "unconnected-(MC1-ADC6-Pad19)") (class "Default")
      (node (ref "MC1") (pin "19") (pinfunction "ADC6_19") (pintype "passive+no_connect"))
    )
    (net (code "56") (name "unconnected-(MC1-ADC7-Pad22)") (class "Default")
      (node (ref "MC1") (pin "22") (pinfunction "ADC7_22") (pintype "passive+no_connect"))
    )
    (net (code "57") (name "unconnected-(U3-R232-Pad15)") (class "Default")
      (node (ref "U3") (pin "15") (pinfunction "R232_15") (pintype "passive+no_connect"))
    )
    (net (code "58") (name "unconnected-(U3-RTS#-Pad14)") (class "Default")
      (node (ref "U3") (pin "14") (pinfunction "RTS#_14") (pintype "passive+no_connect"))
    )
    (net (code "59") (name "unconnected-(U4-+INB-Pad5)") (class "Default")
      (node (ref "U4") (pin "5") (pinfunction "+INB_5") (pintype "passive+no_connect"))
    )
    (net (code "60") (name "unconnected-(U4--INB-Pad6)") (class "Default")
      (node (ref "U4") (pin "6") (pinfunction "-INB_6") (pintype "passive+no_connect"))
    )
    (net (code "61") (name "unconnected-(U4-OUTB-Pad7)") (class "Default")
      (node (ref "U4") (pin "7") (pinfunction "OUTB_7") (pintype "passive+no_connect"))
    )
    (net (code "62") (name "unconnected-(U6-+INA-Pad3)") (class "Default")
      (node (ref "U6") (pin "3") (pinfunction "+INA_3") (pintype "passive+no_connect"))
    )
    (net (code "63") (name "unconnected-(U6--INA-Pad2)") (class "Default")
      (node (ref "U6") (pin "2") (pinfunction "-INA_2") (pintype "passive+no_connect"))
    )
    (net (code "64") (name "unconnected-(U6-OUTA-Pad1)") (class "Default")
      (node (ref "U6") (pin "1") (pinfunction "OUTA_1") (pintype "passive+no_connect"))
    )
  )
)
